# LEDs.net
KiCad netlist of a schematic drawn in Altium Designer
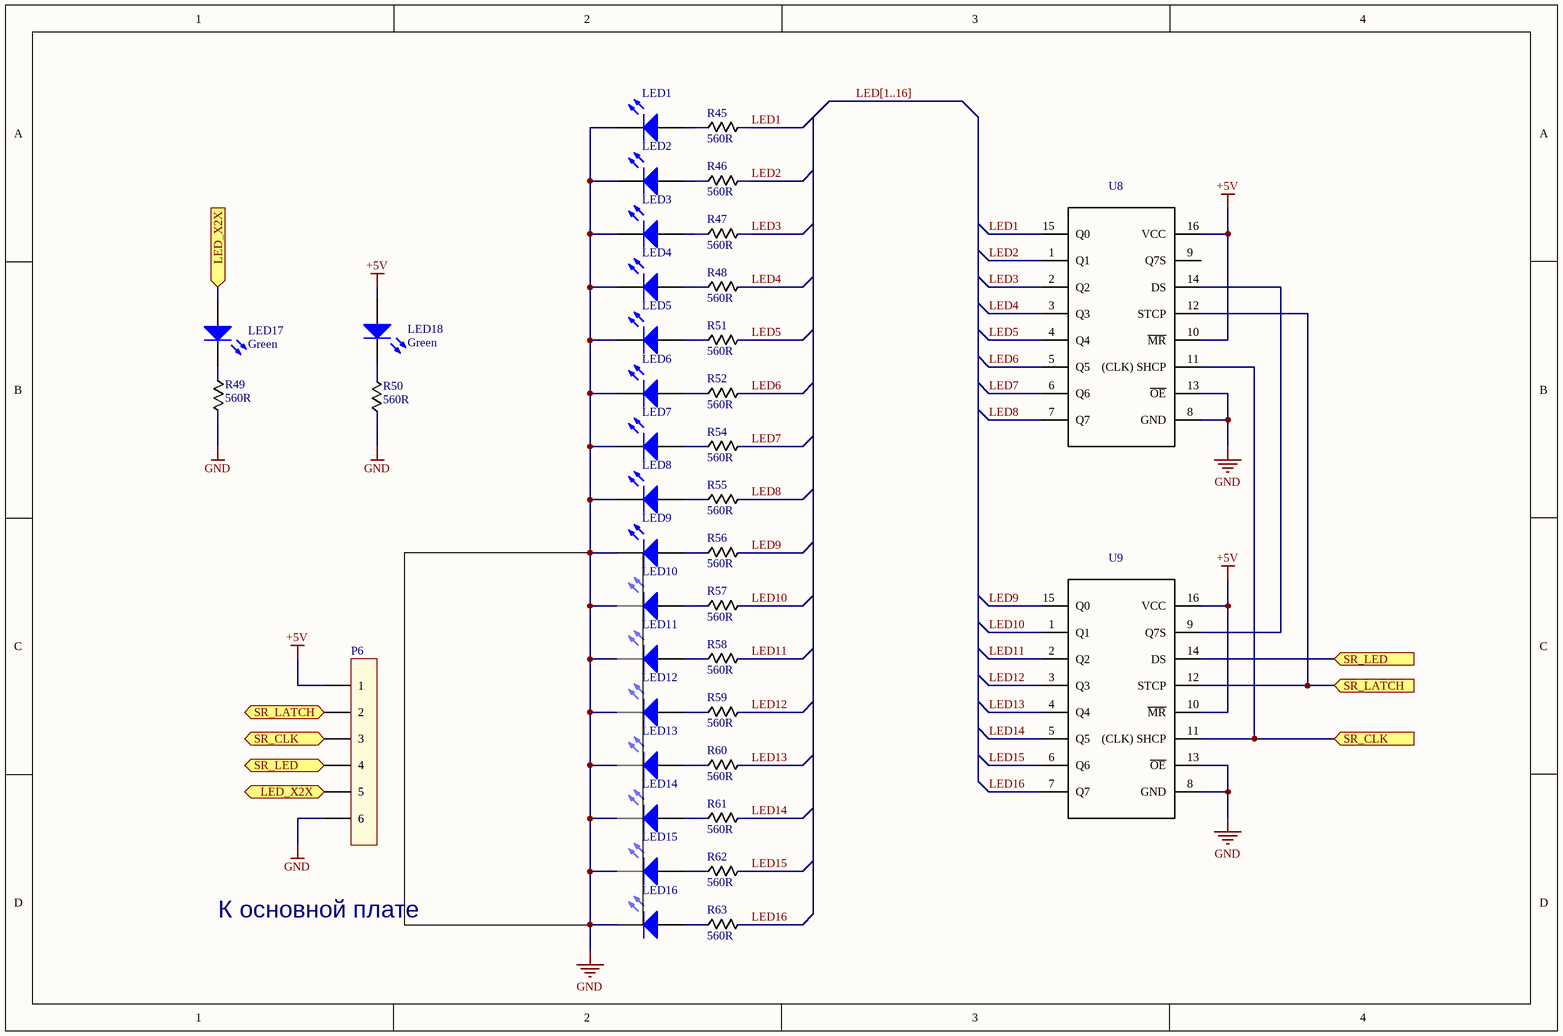
[diagram p0: LEDs.SchDoc]

(export (version "E")
  (design (tool "Eeschema 10.0.6"))
  (components
    (comp (ref "LED1")
      (value "Green")
      (footprint "LED SMD 0603")
      (fields (field (name "PART NUMBER") "KP-1608SGC"))
      (libsource (lib "kontr") (part "0603 LED"))
    )
    (comp (ref "LED2")
      (value "Green")
      (footprint "LED SMD 0603")
      (fields (field (name "PART NUMBER") "KP-1608SGC"))
      (libsource (lib "kontr") (part "0603 LED"))
    )
    (comp (ref "LED3")
      (value "Green")
      (footprint "LED SMD 0603")
      (fields (field (name "PART NUMBER") "KP-1608SGC"))
      (libsource (lib "kontr") (part "0603 LED"))
    )
    (comp (ref "LED4")
      (value "Green")
      (footprint "LED SMD 0603")
      (fields (field (name "PART NUMBER") "KP-1608SGC"))
      (libsource (lib "kontr") (part "0603 LED"))
    )
    (comp (ref "LED5")
      (value "Green")
      (footprint "LED SMD 0603")
      (fields (field (name "PART NUMBER") "KP-1608SGC"))
      (libsource (lib "kontr") (part "0603 LED"))
    )
    (comp (ref "LED6")
      (value "Green")
      (footprint "LED SMD 0603")
      (fields (field (name "PART NUMBER") "KP-1608SGC"))
      (libsource (lib "kontr") (part "0603 LED"))
    )
    (comp (ref "LED7")
      (value "Green")
      (footprint "LED SMD 0603")
      (fields (field (name "PART NUMBER") "KP-1608SGC"))
      (libsource (lib "kontr") (part "0603 LED"))
    )
    (comp (ref "LED8")
      (value "Green")
      (footprint "LED SMD 0603")
      (fields (field (name "PART NUMBER") "KP-1608SGC"))
      (libsource (lib "kontr") (part "0603 LED"))
    )
    (comp (ref "LED9")
      (value "Green")
      (footprint "LED SMD 0603")
      (fields (field (name "PART NUMBER") "KP-1608SGC"))
      (libsource (lib "kontr") (part "0603 LED"))
    )
    (comp (ref "LED10")
      (value "Green")
      (footprint "LED SMD 0603")
      (fields (field (name "PART NUMBER") "KP-1608SGC"))
      (libsource (lib "kontr") (part "0603 LED"))
    )
    (comp (ref "LED11")
      (value "Green")
      (footprint "LED SMD 0603")
      (fields (field (name "PART NUMBER") "KP-1608SGC"))
      (libsource (lib "kontr") (part "0603 LED"))
    )
    (comp (ref "LED12")
      (value "Green")
      (footprint "LED SMD 0603")
      (fields (field (name "PART NUMBER") "KP-1608SGC"))
      (libsource (lib "kontr") (part "0603 LED"))
    )
    (comp (ref "LED13")
      (value "Green")
      (footprint "LED SMD 0603")
      (fields (field (name "PART NUMBER") "KP-1608SGC"))
      (libsource (lib "kontr") (part "0603 LED"))
    )
    (comp (ref "LED14")
      (value "Green")
      (footprint "LED SMD 0603")
      (fields (field (name "PART NUMBER") "KP-1608SGC"))
      (libsource (lib "kontr") (part "0603 LED"))
    )
    (comp (ref "LED15")
      (value "Green")
      (footprint "LED SMD 0603")
      (fields (field (name "PART NUMBER") "KP-1608SGC"))
      (libsource (lib "kontr") (part "0603 LED"))
    )
    (comp (ref "LED16")
      (value "Green")
      (footprint "LED SMD 0603")
      (fields (field (name "PART NUMBER") "KP-1608SGC"))
      (libsource (lib "kontr") (part "0603 LED"))
    )
    (comp (ref "LED17")
      (value "Green")
      (footprint "LED SMD 0603")
      (fields (field (name "PART NUMBER") "KP-1608SGC"))
      (libsource (lib "kontr") (part "0603 LED"))
    )
    (comp (ref "LED18")
      (value "Green")
      (footprint "LED SMD 0603")
      (fields (field (name "PART NUMBER") "KP-1608SGC"))
      (libsource (lib "kontr") (part "0603 LED"))
    )
    (comp (ref "P6")
      (value "~")
      (footprint "МЦТР.00010592.00.002:PLS-6 2.54 - OnlyHoles")
      (fields (field (name "PART NUMBER") "PLS-6"))
      (libsource (lib "levin") (part "PLS-6"))
    )
    (comp (ref "R45")
      (value "560R")
      (footprint "0603_RES")
      (fields (field (name "PART NUMBER") "RC0603JR-07560RL"))
      (libsource (lib "kontr") (part "0603 RES"))
    )
    (comp (ref "R46")
      (value "560R")
      (footprint "0603_RES")
      (fields (field (name "PART NUMBER") "RC0603JR-07560RL"))
      (libsource (lib "kontr") (part "0603 RES"))
    )
    (comp (ref "R47")
      (value "560R")
      (footprint "0603_RES")
      (fields (field (name "PART NUMBER") "RC0603JR-07560RL"))
      (libsource (lib "kontr") (part "0603 RES"))
    )
    (comp (ref "R48")
      (value "560R")
      (footprint "0603_RES")
      (fields (field (name "PART NUMBER") "RC0603JR-07560RL"))
      (libsource (lib "kontr") (part "0603 RES"))
    )
    (comp (ref "R49")
      (value "560R")
      (footprint "0603_RES")
      (fields (field (name "PART NUMBER") "RC0603JR-07560RL"))
      (libsource (lib "kontr") (part "0603 RES"))
    )
    (comp (ref "R50")
      (value "560R")
      (footprint "0603_RES")
      (fields (field (name "PART NUMBER") "RC0603JR-07560RL"))
      (libsource (lib "kontr") (part "0603 RES"))
    )
    (comp (ref "R51")
      (value "560R")
      (footprint "0603_RES")
      (fields (field (name "PART NUMBER") "RC0603JR-07560RL"))
      (libsource (lib "kontr") (part "0603 RES"))
    )
    (comp (ref "R52")
      (value "560R")
      (footprint "0603_RES")
      (fields (field (name "PART NUMBER") "RC0603JR-07560RL"))
      (libsource (lib "kontr") (part "0603 RES"))
    )
    (comp (ref "R54")
      (value "560R")
      (footprint "0603_RES")
      (fields (field (name "PART NUMBER") "RC0603JR-07560RL"))
      (libsource (lib "kontr") (part "0603 RES"))
    )
    (comp (ref "R55")
      (value "560R")
      (footprint "0603_RES")
      (fields (field (name "PART NUMBER") "RC0603JR-07560RL"))
      (libsource (lib "kontr") (part "0603 RES"))
    )
    (comp (ref "R56")
      (value "560R")
      (footprint "0603_RES")
      (fields (field (name "PART NUMBER") "RC0603JR-07560RL"))
      (libsource (lib "kontr") (part "0603 RES"))
    )
    (comp (ref "R57")
      (value "560R")
      (footprint "0603_RES")
      (fields (field (name "PART NUMBER") "RC0603JR-07560RL"))
      (libsource (lib "kontr") (part "0603 RES"))
    )
    (comp (ref "R58")
      (value "560R")
      (footprint "0603_RES")
      (fields (field (name "PART NUMBER") "RC0603JR-07560RL"))
      (libsource (lib "kontr") (part "0603 RES"))
    )
    (comp (ref "R59")
      (value "560R")
      (footprint "0603_RES")
      (fields (field (name "PART NUMBER") "RC0603JR-07560RL"))
      (libsource (lib "kontr") (part "0603 RES"))
    )
    (comp (ref "R60")
      (value "560R")
      (footprint "0603_RES")
      (fields (field (name "PART NUMBER") "RC0603JR-07560RL"))
      (libsource (lib "kontr") (part "0603 RES"))
    )
    (comp (ref "R61")
      (value "560R")
      (footprint "0603_RES")
      (fields (field (name "PART NUMBER") "RC0603JR-07560RL"))
      (libsource (lib "kontr") (part "0603 RES"))
    )
    (comp (ref "R62")
      (value "560R")
      (footprint "0603_RES")
      (fields (field (name "PART NUMBER") "RC0603JR-07560RL"))
      (libsource (lib "kontr") (part "0603 RES"))
    )
    (comp (ref "R63")
      (value "560R")
      (footprint "0603_RES")
      (fields (field (name "PART NUMBER") "RC0603JR-07560RL"))
      (libsource (lib "kontr") (part "0603 RES"))
    )
    (comp (ref "U8")
      (value "~")
      (footprint "SOIC 16")
      (fields (field (name "PART NUMBER") "74HC595D.118"))
      (libsource (lib "74hc595") (part "74HC595"))
    )
    (comp (ref "U9")
      (value "~")
      (footprint "SOIC 16")
      (fields (field (name "PART NUMBER") "74HC595D.118"))
      (libsource (lib "74hc595") (part "74HC595"))
    )
  )
  (nets
    (net (code "1") (name "+5V") (class "Default")
      (node (ref "LED18") (pin "1") (pinfunction "A_1") (pintype "passive"))
      (node (ref "P6") (pin "1") (pinfunction "1_1") (pintype "passive"))
      (node (ref "U8") (pin "10") (pinfunction "~{MR}_10") (pintype "passive"))
      (node (ref "U8") (pin "16") (pinfunction "VCC_16") (pintype "passive"))
      (node (ref "U9") (pin "10") (pinfunction "~{MR}_10") (pintype "passive"))
      (node (ref "U9") (pin "16") (pinfunction "VCC_16") (pintype "passive"))
    )
    (net (code "2") (name "/LED1") (class "Default")
      (node (ref "R45") (pin "2") (pintype "passive"))
      (node (ref "U8") (pin "15") (pinfunction "Q0_15") (pintype "passive"))
    )
    (net (code "3") (name "/LED2") (class "Default")
      (node (ref "R46") (pin "2") (pintype "passive"))
      (node (ref "U8") (pin "1") (pinfunction "Q1_1") (pintype "passive"))
    )
    (net (code "4") (name "/LED3") (class "Default")
      (node (ref "R47") (pin "2") (pintype "passive"))
      (node (ref "U8") (pin "2") (pinfunction "Q2_2") (pintype "passive"))
    )
    (net (code "5") (name "/LED4") (class "Default")
      (node (ref "R48") (pin "2") (pintype "passive"))
      (node (ref "U8") (pin "3") (pinfunction "Q3_3") (pintype "passive"))
    )
    (net (code "6") (name "/LED5") (class "Default")
      (node (ref "R51") (pin "2") (pintype "passive"))
      (node (ref "U8") (pin "4") (pinfunction "Q4_4") (pintype "passive"))
    )
    (net (code "7") (name "/LED6") (class "Default")
      (node (ref "R52") (pin "2") (pintype "passive"))
      (node (ref "U8") (pin "5") (pinfunction "Q5_5") (pintype "passive"))
    )
    (net (code "8") (name "/LED7") (class "Default")
      (node (ref "R54") (pin "2") (pintype "passive"))
      (node (ref "U8") (pin "6") (pinfunction "Q6_6") (pintype "passive"))
    )
    (net (code "9") (name "/LED8") (class "Default")
      (node (ref "R55") (pin "2") (pintype "passive"))
      (node (ref "U8") (pin "7") (pinfunction "Q7_7") (pintype "passive"))
    )
    (net (code "10") (name "/LED9") (class "Default")
      (node (ref "R56") (pin "2") (pintype "passive"))
      (node (ref "U9") (pin "15") (pinfunction "Q0_15") (pintype "passive"))
    )
    (net (code "11") (name "/LED10") (class "Default")
      (node (ref "R57") (pin "2") (pintype "passive"))
      (node (ref "U9") (pin "1") (pinfunction "Q1_1") (pintype "passive"))
    )
    (net (code "12") (name "/LED11") (class "Default")
      (node (ref "R58") (pin "2") (pintype "passive"))
      (node (ref "U9") (pin "2") (pinfunction "Q2_2") (pintype "passive"))
    )
    (net (code "13") (name "/LED12") (class "Default")
      (node (ref "R59") (pin "2") (pintype "passive"))
      (node (ref "U9") (pin "3") (pinfunction "Q3_3") (pintype "passive"))
    )
    (net (code "14") (name "/LED13") (class "Default")
      (node (ref "R60") (pin "2") (pintype "passive"))
      (node (ref "U9") (pin "4") (pinfunction "Q4_4") (pintype "passive"))
    )
    (net (code "15") (name "/LED14") (class "Default")
      (node (ref "R61") (pin "2") (pintype "passive"))
      (node (ref "U9") (pin "5") (pinfunction "Q5_5") (pintype "passive"))
    )
    (net (code "16") (name "/LED15") (class "Default")
      (node (ref "R62") (pin "2") (pintype "passive"))
      (node (ref "U9") (pin "6") (pinfunction "Q6_6") (pintype "passive"))
    )
    (net (code "17") (name "/LED16") (class "Default")
      (node (ref "R63") (pin "2") (pintype "passive"))
      (node (ref "U9") (pin "7") (pinfunction "Q7_7") (pintype "passive"))
    )
    (net (code "19") (name "/LED_X2X") (class "Default")
      (node (ref "LED17") (pin "1") (pinfunction "A_1") (pintype "passive"))
      (node (ref "P6") (pin "5") (pinfunction "5_5") (pintype "passive"))
    )
    (net (code "20") (name "/SR_CLK") (class "Default")
      (node (ref "P6") (pin "3") (pinfunction "3_3") (pintype "passive"))
      (node (ref "U8") (pin "11") (pinfunction "(CLK)_SHCP_11") (pintype "passive"))
      (node (ref "U9") (pin "11") (pinfunction "(CLK)_SHCP_11") (pintype "passive"))
    )
    (net (code "21") (name "/SR_LATCH") (class "Default")
      (node (ref "P6") (pin "2") (pinfunction "2_2") (pintype "passive"))
      (node (ref "U8") (pin "12") (pinfunction "STCP_12") (pintype "passive"))
      (node (ref "U9") (pin "12") (pinfunction "STCP_12") (pintype "passive"))
    )
    (net (code "22") (name "/SR_LED") (class "Default")
      (node (ref "P6") (pin "4") (pinfunction "4_4") (pintype "passive"))
      (node (ref "U9") (pin "14") (pinfunction "DS_14") (pintype "passive"))
    )
    (net (code "23") (name "GND") (class "Default")
      (node (ref "LED1") (pin "2") (pinfunction "K_2") (pintype "passive"))
      (node (ref "LED10") (pin "2") (pinfunction "K_2") (pintype "passive"))
      (node (ref "LED11") (pin "2") (pinfunction "K_2") (pintype "passive"))
      (node (ref "LED12") (pin "2") (pinfunction "K_2") (pintype "passive"))
      (node (ref "LED13") (pin "2") (pinfunction "K_2") (pintype "passive"))
      (node (ref "LED14") (pin "2") (pinfunction "K_2") (pintype "passive"))
      (node (ref "LED15") (pin "2") (pinfunction "K_2") (pintype "passive"))
      (node (ref "LED16") (pin "2") (pinfunction "K_2") (pintype "passive"))
      (node (ref "LED2") (pin "2") (pinfunction "K_2") (pintype "passive"))
      (node (ref "LED3") (pin "2") (pinfunction "K_2") (pintype "passive"))
      (node (ref "LED4") (pin "2") (pinfunction "K_2") (pintype "passive"))
      (node (ref "LED5") (pin "2") (pinfunction "K_2") (pintype "passive"))
      (node (ref "LED6") (pin "2") (pinfunction "K_2") (pintype "passive"))
      (node (ref "LED7") (pin "2") (pinfunction "K_2") (pintype "passive"))
      (node (ref "LED8") (pin "2") (pinfunction "K_2") (pintype "passive"))
      (node (ref "LED9") (pin "2") (pinfunction "K_2") (pintype "passive"))
      (node (ref "P6") (pin "6") (pinfunction "6_6") (pintype "passive"))
      (node (ref "R49") (pin "2") (pintype "passive"))
      (node (ref "R50") (pin "1") (pintype "passive"))
      (node (ref "U8") (pin "13") (pinfunction "~{OE}_13") (pintype "passive"))
      (node (ref "U8") (pin "8") (pinfunction "GND_8") (pintype "passive"))
      (node (ref "U9") (pin "13") (pinfunction "~{OE}_13") (pintype "passive"))
      (node (ref "U9") (pin "8") (pinfunction "GND_8") (pintype "passive"))
    )
    (net (code "24") (name "Net-(LED1-A)") (class "Default")
      (node (ref "LED1") (pin "1") (pinfunction "A_1") (pintype "passive"))
      (node (ref "R45") (pin "1") (pintype "passive"))
    )
    (net (code "25") (name "Net-(LED2-A)") (class "Default")
      (node (ref "LED2") (pin "1") (pinfunction "A_1") (pintype "passive"))
      (node (ref "R46") (pin "1") (pintype "passive"))
    )
    (net (code "26") (name "Net-(LED3-A)") (class "Default")
      (node (ref "LED3") (pin "1") (pinfunction "A_1") (pintype "passive"))
      (node (ref "R47") (pin "1") (pintype "passive"))
    )
    (net (code "27") (name "Net-(LED4-A)") (class "Default")
      (node (ref "LED4") (pin "1") (pinfunction "A_1") (pintype "passive"))
      (node (ref "R48") (pin "1") (pintype "passive"))
    )
    (net (code "28") (name "Net-(LED5-A)") (class "Default")
      (node (ref "LED5") (pin "1") (pinfunction "A_1") (pintype "passive"))
      (node (ref "R51") (pin "1") (pintype "passive"))
    )
    (net (code "29") (name "Net-(LED6-A)") (class "Default")
      (node (ref "LED6") (pin "1") (pinfunction "A_1") (pintype "passive"))
      (node (ref "R52") (pin "1") (pintype "passive"))
    )
    (net (code "30") (name "Net-(LED7-A)") (class "Default")
      (node (ref "LED7") (pin "1") (pinfunction "A_1") (pintype "passive"))
      (node (ref "R54") (pin "1") (pintype "passive"))
    )
    (net (code "31") (name "Net-(LED8-A)") (class "Default")
      (node (ref "LED8") (pin "1") (pinfunction "A_1") (pintype "passive"))
      (node (ref "R55") (pin "1") (pintype "passive"))
    )
    (net (code "32") (name "Net-(LED9-A)") (class "Default")
      (node (ref "LED9") (pin "1") (pinfunction "A_1") (pintype "passive"))
      (node (ref "R56") (pin "1") (pintype "passive"))
    )
    (net (code "33") (name "Net-(LED10-A)") (class "Default")
      (node (ref "LED10") (pin "1") (pinfunction "A_1") (pintype "passive"))
      (node (ref "R57") (pin "1") (pintype "passive"))
    )
    (net (code "34") (name "Net-(LED11-A)") (class "Default")
      (node (ref "LED11") (pin "1") (pinfunction "A_1") (pintype "passive"))
      (node (ref "R58") (pin "1") (pintype "passive"))
    )
    (net (code "35") (name "Net-(LED12-A)") (class "Default")
      (node (ref "LED12") (pin "1") (pinfunction "A_1") (pintype "passive"))
      (node (ref "R59") (pin "1") (pintype "passive"))
    )
    (net (code "36") (name "Net-(LED13-A)") (class "Default")
      (node (ref "LED13") (pin "1") (pinfunction "A_1") (pintype "passive"))
      (node (ref "R60") (pin "1") (pintype "passive"))
    )
    (net (code "37") (name "Net-(LED14-A)") (class "Default")
      (node (ref "LED14") (pin "1") (pinfunction "A_1") (pintype "passive"))
      (node (ref "R61") (pin "1") (pintype "passive"))
    )
    (net (code "38") (name "Net-(LED15-A)") (class "Default")
      (node (ref "LED15") (pin "1") (pinfunction "A_1") (pintype "passive"))
      (node (ref "R62") (pin "1") (pintype "passive"))
    )
    (net (code "39") (name "Net-(LED16-A)") (class "Default")
      (node (ref "LED16") (pin "1") (pinfunction "A_1") (pintype "passive"))
      (node (ref "R63") (pin "1") (pintype "passive"))
    )
    (net (code "40") (name "Net-(LED17-K)") (class "Default")
      (node (ref "LED17") (pin "2") (pinfunction "K_2") (pintype "passive"))
      (node (ref "R49") (pin "1") (pintype "passive"))
    )
    (net (code "41") (name "Net-(LED18-K)") (class "Default")
      (node (ref "LED18") (pin "2") (pinfunction "K_2") (pintype "passive"))
      (node (ref "R50") (pin "2") (pintype "passive"))
    )
    (net (code "42") (name "Net-(U8-DS)") (class "Default")
      (node (ref "U8") (pin "14") (pinfunction "DS_14") (pintype "passive"))
      (node (ref "U9") (pin "9") (pinfunction "Q7S_9") (pintype "passive"))
    )
    (net (code "43") (name "unconnected-(U8-Q7S-Pad9)") (class "Default")
      (node (ref "U8") (pin "9") (pinfunction "Q7S_9") (pintype "passive"))
    )
  )
)
